# FlyControl.net
KiCad netlist of a schematic drawn in Altium Designer
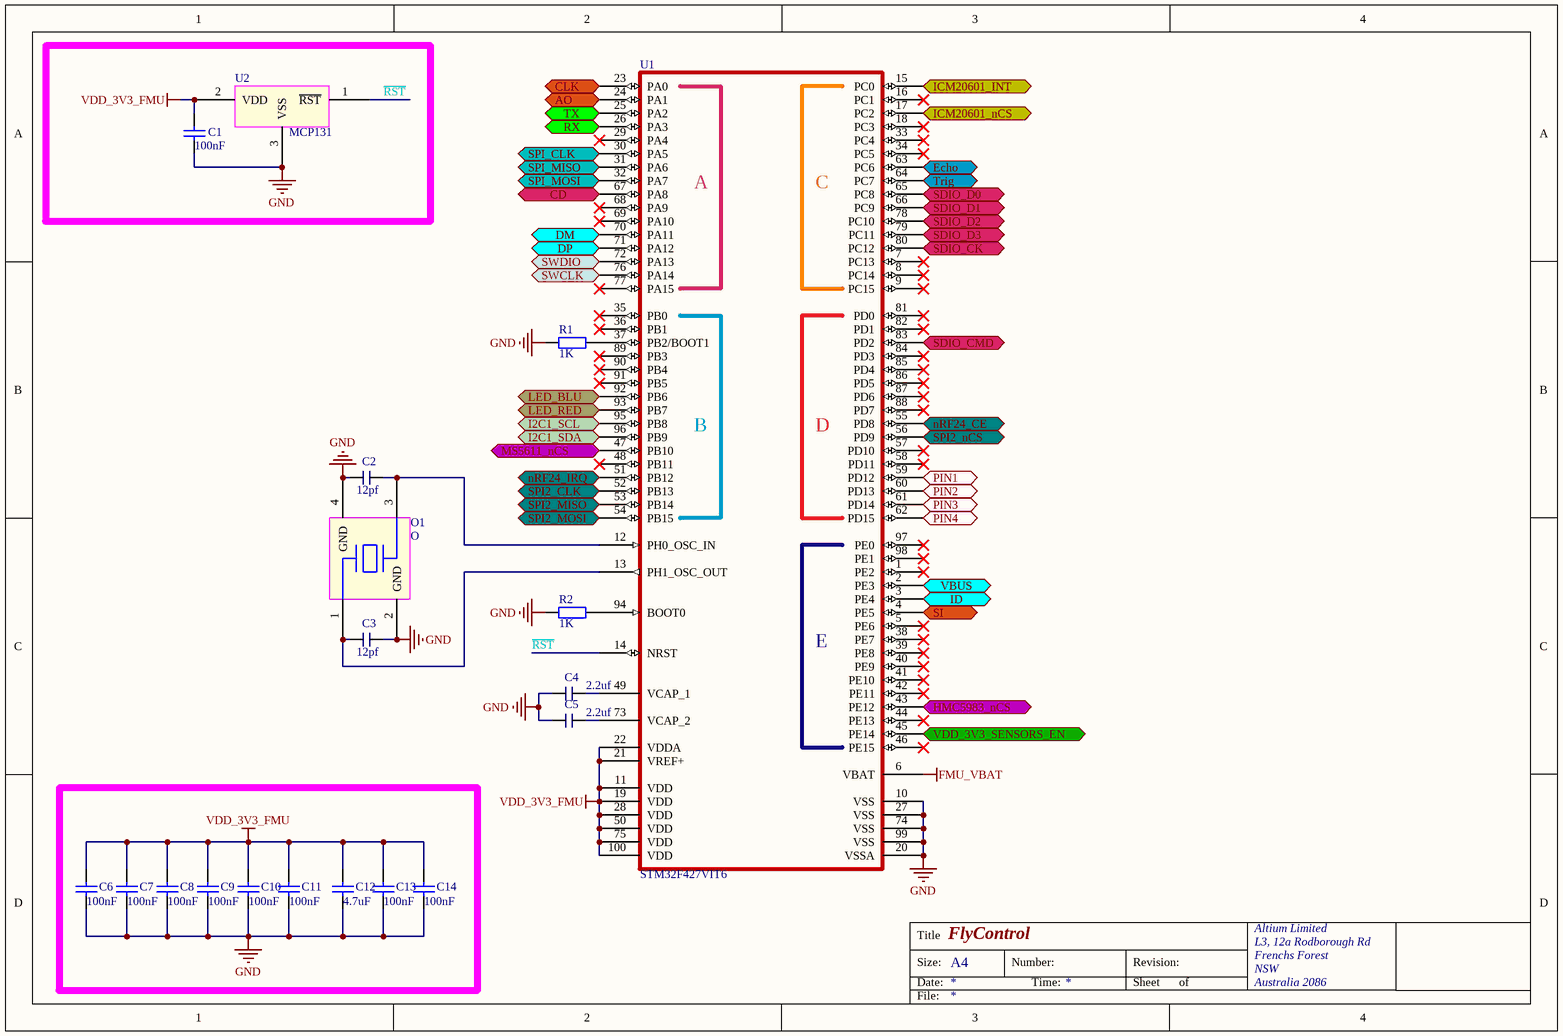
[diagram p0: FlyControl.SchDoc]

(export (version "E")
  (design (tool "Eeschema 10.0.6"))
  (components
    (comp (ref "C1")
      (value "100nF")
      (footprint "0603AC")
      (description "Capacitor")
      (fields (field (name "Comment") "Cap1") (field (name "PUBLISHER") "Altium Limited"))
      (libsource (lib "Component") (part "Cap1"))
    )
    (comp (ref "C2")
      (value "12pf")
      (footprint "0603AC")
      (fields (field (name "Comment") "Capacity"))
      (libsource (lib "Component") (part "Cap"))
    )
    (comp (ref "C3")
      (value "12pf")
      (footprint "0603AC")
      (fields (field (name "Comment") "Capacity"))
      (libsource (lib "Component") (part "Cap"))
    )
    (comp (ref "C4")
      (value "2.2uf")
      (footprint "0603AC")
      (fields (field (name "Comment") "Capacity"))
      (libsource (lib "Component") (part "Cap"))
    )
    (comp (ref "C5")
      (value "2.2uf")
      (footprint "0603AC")
      (fields (field (name "Comment") "Capacity"))
      (libsource (lib "Component") (part "Cap"))
    )
    (comp (ref "C6")
      (value "100nF")
      (footprint "0603AC")
      (description "Capacitor")
      (fields (field (name "Comment") "Cap1") (field (name "PUBLISHER") "Altium Limited"))
      (libsource (lib "Component") (part "Cap1"))
    )
    (comp (ref "C7")
      (value "100nF")
      (footprint "0603AC")
      (description "Capacitor")
      (fields (field (name "Comment") "Cap1") (field (name "PUBLISHER") "Altium Limited"))
      (libsource (lib "Component") (part "Cap1"))
    )
    (comp (ref "C8")
      (value "100nF")
      (footprint "0603AC")
      (description "Capacitor")
      (fields (field (name "Comment") "Cap1") (field (name "PUBLISHER") "Altium Limited"))
      (libsource (lib "Component") (part "Cap1"))
    )
    (comp (ref "C9")
      (value "100nF")
      (footprint "0603AC")
      (description "Capacitor")
      (fields (field (name "Comment") "Cap1") (field (name "PUBLISHER") "Altium Limited"))
      (libsource (lib "Component") (part "Cap1"))
    )
    (comp (ref "C10")
      (value "100nF")
      (footprint "0603AC")
      (description "Capacitor")
      (fields (field (name "Comment") "Cap1") (field (name "PUBLISHER") "Altium Limited"))
      (libsource (lib "Component") (part "Cap1"))
    )
    (comp (ref "C11")
      (value "100nF")
      (footprint "0603AC")
      (description "Capacitor")
      (fields (field (name "Comment") "Cap1") (field (name "PUBLISHER") "Altium Limited"))
      (libsource (lib "Component") (part "Cap1"))
    )
    (comp (ref "C12")
      (value "4.7uF")
      (footprint "0603AC")
      (description "Capacitor")
      (fields (field (name "Comment") "Cap1") (field (name "PUBLISHER") "Altium Limited"))
      (libsource (lib "Component") (part "Cap1"))
    )
    (comp (ref "C13")
      (value "100nF")
      (footprint "0603AC")
      (description "Capacitor")
      (fields (field (name "Comment") "Cap1") (field (name "PUBLISHER") "Altium Limited"))
      (libsource (lib "Component") (part "Cap1"))
    )
    (comp (ref "C14")
      (value "100nF")
      (footprint "0603AC")
      (description "Capacitor")
      (fields (field (name "Comment") "Cap1") (field (name "PUBLISHER") "Altium Limited"))
      (libsource (lib "Component") (part "Cap1"))
    )
    (comp (ref "O1") (value "O") (footprint "SMD_3225") (libsource (lib "Component") (part "OSC")))
    (comp (ref "R1")
      (value "1K")
      (footprint "0603AR")
      (fields (field (name "Comment") "Resist"))
      (libsource (lib "Component") (part "Res"))
    )
    (comp (ref "R2")
      (value "1K")
      (footprint "0603AR")
      (fields (field (name "Comment") "Resist"))
      (libsource (lib "Component") (part "Res"))
    )
    (comp (ref "U1")
      (value "STM32F427VIT6")
      (footprint "LQFP50P1600X1600X160-100N")
      (libsource (lib "Microprocessor") (part "STM32F427VIT6"))
    )
    (comp (ref "U2") (value "MCP131") (footprint "SOT23") (libsource (lib "Reset") (part "MCP131")))
  )
  (nets
    (net (code "1") (name "/AO") (class "Default")
      (node (ref "U1") (pin "24") (pinfunction "PA1_24") (pintype "bidirectional"))
    )
    (net (code "2") (name "/CD") (class "Default")
      (node (ref "U1") (pin "67") (pinfunction "PA8_67") (pintype "bidirectional"))
    )
    (net (code "3") (name "/CLK") (class "Default")
      (node (ref "U1") (pin "23") (pinfunction "PA0_23") (pintype "bidirectional"))
    )
    (net (code "4") (name "/DM") (class "Default")
      (node (ref "U1") (pin "70") (pinfunction "PA11_70") (pintype "bidirectional"))
    )
    (net (code "5") (name "/DP") (class "Default")
      (node (ref "U1") (pin "71") (pinfunction "PA12_71") (pintype "bidirectional"))
    )
    (net (code "6") (name "/Echo") (class "Default")
      (node (ref "U1") (pin "63") (pinfunction "PC6_63") (pintype "bidirectional"))
    )
    (net (code "7") (name "/HMC5983_nCS") (class "Default")
      (node (ref "U1") (pin "43") (pinfunction "PE12_43") (pintype "bidirectional"))
    )
    (net (code "8") (name "/I2C1_SCL") (class "Default")
      (node (ref "U1") (pin "95") (pinfunction "PB8_95") (pintype "bidirectional"))
    )
    (net (code "9") (name "/I2C1_SDA") (class "Default")
      (node (ref "U1") (pin "96") (pinfunction "PB9_96") (pintype "bidirectional"))
    )
    (net (code "10") (name "/ICM20601_INT") (class "Default")
      (node (ref "U1") (pin "15") (pinfunction "PC0_15") (pintype "bidirectional"))
    )
    (net (code "11") (name "/ICM20601_nCS") (class "Default")
      (node (ref "U1") (pin "17") (pinfunction "PC2_17") (pintype "bidirectional"))
    )
    (net (code "12") (name "/ID") (class "Default")
      (node (ref "U1") (pin "3") (pinfunction "PE4_3") (pintype "bidirectional"))
    )
    (net (code "13") (name "/LED_BLU") (class "Default")
      (node (ref "U1") (pin "92") (pinfunction "PB6_92") (pintype "bidirectional"))
    )
    (net (code "14") (name "/LED_RED") (class "Default")
      (node (ref "U1") (pin "93") (pinfunction "PB7_93") (pintype "bidirectional"))
    )
    (net (code "15") (name "/MS5611_nCS") (class "Default")
      (node (ref "U1") (pin "47") (pinfunction "PB10_47") (pintype "bidirectional"))
    )
    (net (code "16") (name "/PIN1") (class "Default")
      (node (ref "U1") (pin "59") (pinfunction "PD12_59") (pintype "bidirectional"))
    )
    (net (code "17") (name "/PIN2") (class "Default")
      (node (ref "U1") (pin "60") (pinfunction "PD13_60") (pintype "bidirectional"))
    )
    (net (code "18") (name "/PIN3") (class "Default")
      (node (ref "U1") (pin "61") (pinfunction "PD14_61") (pintype "bidirectional"))
    )
    (net (code "19") (name "/PIN4") (class "Default")
      (node (ref "U1") (pin "62") (pinfunction "PD15_62") (pintype "bidirectional"))
    )
    (net (code "20") (name "/RX") (class "Default")
      (node (ref "U1") (pin "26") (pinfunction "PA3_26") (pintype "bidirectional"))
    )
    (net (code "21") (name "/SDIO_CK") (class "Default")
      (node (ref "U1") (pin "80") (pinfunction "PC12_80") (pintype "bidirectional"))
    )
    (net (code "22") (name "/SDIO_CMD") (class "Default")
      (node (ref "U1") (pin "83") (pinfunction "PD2_83") (pintype "bidirectional"))
    )
    (net (code "23") (name "/SDIO_D0") (class "Default")
      (node (ref "U1") (pin "65") (pinfunction "PC8_65") (pintype "bidirectional"))
    )
    (net (code "24") (name "/SDIO_D1") (class "Default")
      (node (ref "U1") (pin "66") (pinfunction "PC9_66") (pintype "bidirectional"))
    )
    (net (code "25") (name "/SDIO_D2") (class "Default")
      (node (ref "U1") (pin "78") (pinfunction "PC10_78") (pintype "bidirectional"))
    )
    (net (code "26") (name "/SDIO_D3") (class "Default")
      (node (ref "U1") (pin "79") (pinfunction "PC11_79") (pintype "bidirectional"))
    )
    (net (code "27") (name "/SI") (class "Default")
      (node (ref "U1") (pin "4") (pinfunction "PE5_4") (pintype "bidirectional"))
    )
    (net (code "28") (name "/SPI2_CLK") (class "Default")
      (node (ref "U1") (pin "52") (pinfunction "PB13_52") (pintype "bidirectional"))
    )
    (net (code "29") (name "/SPI2_MISO") (class "Default")
      (node (ref "U1") (pin "53") (pinfunction "PB14_53") (pintype "bidirectional"))
    )
    (net (code "30") (name "/SPI2_MOSI") (class "Default")
      (node (ref "U1") (pin "54") (pinfunction "PB15_54") (pintype "bidirectional"))
    )
    (net (code "31") (name "/SPI2_nCS") (class "Default")
      (node (ref "U1") (pin "56") (pinfunction "PD9_56") (pintype "bidirectional"))
    )
    (net (code "32") (name "/SPI_CLK") (class "Default")
      (node (ref "U1") (pin "30") (pinfunction "PA5_30") (pintype "bidirectional"))
    )
    (net (code "33") (name "/SPI_MISO") (class "Default")
      (node (ref "U1") (pin "31") (pinfunction "PA6_31") (pintype "bidirectional"))
    )
    (net (code "34") (name "/SPI_MOSI") (class "Default")
      (node (ref "U1") (pin "32") (pinfunction "PA7_32") (pintype "bidirectional"))
    )
    (net (code "35") (name "/SWCLK") (class "Default")
      (node (ref "U1") (pin "76") (pinfunction "PA14_76") (pintype "bidirectional"))
    )
    (net (code "36") (name "/SWDIO") (class "Default")
      (node (ref "U1") (pin "72") (pinfunction "PA13_72") (pintype "bidirectional"))
    )
    (net (code "37") (name "/TX") (class "Default")
      (node (ref "U1") (pin "25") (pinfunction "PA2_25") (pintype "bidirectional"))
    )
    (net (code "38") (name "/Trig") (class "Default")
      (node (ref "U1") (pin "64") (pinfunction "PC7_64") (pintype "bidirectional"))
    )
    (net (code "39") (name "/VBUS") (class "Default")
      (node (ref "U1") (pin "2") (pinfunction "PE3_2") (pintype "bidirectional"))
    )
    (net (code "40") (name "/VDD_3V3_SENSORS_EN") (class "Default")
      (node (ref "U1") (pin "45") (pinfunction "PE14_45") (pintype "bidirectional"))
    )
    (net (code "41") (name "/nRF24_CE") (class "Default")
      (node (ref "U1") (pin "55") (pinfunction "PD8_55") (pintype "bidirectional"))
    )
    (net (code "42") (name "/nRF24_IRQ") (class "Default")
      (node (ref "U1") (pin "51") (pinfunction "PB12_51") (pintype "bidirectional"))
    )
    (net (code "43") (name "/~{RST}") (class "Default")
      (node (ref "U1") (pin "14") (pinfunction "NRST_14") (pintype "bidirectional"))
      (node (ref "U2") (pin "1") (pinfunction "~{RST}_1") (pintype "passive"))
    )
    (net (code "44") (name "FMU_VBAT") (class "Default")
      (node (ref "U1") (pin "6") (pinfunction "VBAT_6") (pintype "power_in"))
    )
    (net (code "45") (name "GND") (class "Default")
      (node (ref "C1") (pin "1") (pinfunction "1_1") (pintype "passive"))
      (node (ref "C10") (pin "1") (pinfunction "1_1") (pintype "passive"))
      (node (ref "C11") (pin "1") (pinfunction "1_1") (pintype "passive"))
      (node (ref "C12") (pin "1") (pinfunction "1_1") (pintype "passive"))
      (node (ref "C13") (pin "1") (pinfunction "1_1") (pintype "passive"))
      (node (ref "C14") (pin "1") (pinfunction "1_1") (pintype "passive"))
      (node (ref "C2") (pin "1") (pinfunction "1_1") (pintype "passive"))
      (node (ref "C3") (pin "2") (pinfunction "2_2") (pintype "passive"))
      (node (ref "C4") (pin "1") (pinfunction "1_1") (pintype "passive"))
      (node (ref "C5") (pin "1") (pinfunction "1_1") (pintype "passive"))
      (node (ref "C6") (pin "1") (pinfunction "1_1") (pintype "passive"))
      (node (ref "C7") (pin "1") (pinfunction "1_1") (pintype "passive"))
      (node (ref "C8") (pin "1") (pinfunction "1_1") (pintype "passive"))
      (node (ref "C9") (pin "1") (pinfunction "1_1") (pintype "passive"))
      (node (ref "O1") (pin "2") (pinfunction "GND_2") (pintype "passive"))
      (node (ref "O1") (pin "4") (pinfunction "GND_4") (pintype "passive"))
      (node (ref "R1") (pin "1") (pinfunction "1_1") (pintype "passive"))
      (node (ref "R2") (pin "1") (pinfunction "1_1") (pintype "passive"))
      (node (ref "U1") (pin "10") (pinfunction "VSS_10") (pintype "power_in"))
      (node (ref "U1") (pin "20") (pinfunction "VSSA_20") (pintype "power_in"))
      (node (ref "U1") (pin "27") (pinfunction "VSS_27") (pintype "power_in"))
      (node (ref "U1") (pin "74") (pinfunction "VSS_74") (pintype "power_in"))
      (node (ref "U1") (pin "99") (pinfunction "VSS_99") (pintype "power_in"))
      (node (ref "U2") (pin "3") (pinfunction "VSS_3") (pintype "passive"))
    )
    (net (code "46") (name "Net-(U1-BOOT0)") (class "Default")
      (node (ref "R2") (pin "2") (pinfunction "2_2") (pintype "passive"))
      (node (ref "U1") (pin "94") (pinfunction "BOOT0_94") (pintype "input"))
    )
    (net (code "47") (name "Net-(U1-PB2{slash}BOOT1)") (class "Default")
      (node (ref "R1") (pin "2") (pinfunction "2_2") (pintype "passive"))
      (node (ref "U1") (pin "37") (pinfunction "PB2/BOOT1_37") (pintype "bidirectional"))
    )
    (net (code "48") (name "Net-(U1-PH0_OSC_IN)") (class "Default")
      (node (ref "C2") (pin "2") (pinfunction "2_2") (pintype "passive"))
      (node (ref "O1") (pin "3") (pinfunction "OSC_3") (pintype "passive"))
      (node (ref "U1") (pin "12") (pinfunction "PH0_OSC_IN_12") (pintype "input"))
    )
    (net (code "49") (name "Net-(U1-PH1_OSC_OUT)") (class "Default")
      (node (ref "C3") (pin "1") (pinfunction "1_1") (pintype "passive"))
      (node (ref "O1") (pin "1") (pinfunction "OSC_1") (pintype "passive"))
      (node (ref "U1") (pin "13") (pinfunction "PH1_OSC_OUT_13") (pintype "output"))
    )
    (net (code "50") (name "Net-(U1-VCAP_1)") (class "Default")
      (node (ref "C4") (pin "2") (pinfunction "2_2") (pintype "passive"))
      (node (ref "U1") (pin "49") (pinfunction "VCAP_1_49") (pintype "passive"))
    )
    (net (code "51") (name "Net-(U1-VCAP_2)") (class "Default")
      (node (ref "C5") (pin "2") (pinfunction "2_2") (pintype "passive"))
      (node (ref "U1") (pin "73") (pinfunction "VCAP_2_73") (pintype "passive"))
    )
    (net (code "52") (name "VDD_3V3_FMU") (class "Default")
      (node (ref "C1") (pin "2") (pinfunction "2_2") (pintype "passive"))
      (node (ref "C10") (pin "2") (pinfunction "2_2") (pintype "passive"))
      (node (ref "C11") (pin "2") (pinfunction "2_2") (pintype "passive"))
      (node (ref "C12") (pin "2") (pinfunction "2_2") (pintype "passive"))
      (node (ref "C13") (pin "2") (pinfunction "2_2") (pintype "passive"))
      (node (ref "C14") (pin "2") (pinfunction "2_2") (pintype "passive"))
      (node (ref "C6") (pin "2") (pinfunction "2_2") (pintype "passive"))
      (node (ref "C7") (pin "2") (pinfunction "2_2") (pintype "passive"))
      (node (ref "C8") (pin "2") (pinfunction "2_2") (pintype "passive"))
      (node (ref "C9") (pin "2") (pinfunction "2_2") (pintype "passive"))
      (node (ref "U1") (pin "100") (pinfunction "VDD_100") (pintype "power_in"))
      (node (ref "U1") (pin "11") (pinfunction "VDD_11") (pintype "power_in"))
      (node (ref "U1") (pin "19") (pinfunction "VDD_19") (pintype "power_in"))
      (node (ref "U1") (pin "21") (pinfunction "VREF+_21") (pintype "power_in"))
      (node (ref "U1") (pin "22") (pinfunction "VDDA_22") (pintype "power_in"))
      (node (ref "U1") (pin "28") (pinfunction "VDD_28") (pintype "power_in"))
      (node (ref "U1") (pin "50") (pinfunction "VDD_50") (pintype "power_in"))
      (node (ref "U1") (pin "75") (pinfunction "VDD_75") (pintype "power_in"))
      (node (ref "U2") (pin "2") (pinfunction "VDD_2") (pintype "passive"))
    )
    (net (code "53") (name "unconnected-(U1-PA4-Pad29)") (class "Default")
      (node (ref "U1") (pin "29") (pinfunction "PA4_29") (pintype "bidirectional+no_connect"))
    )
    (net (code "54") (name "unconnected-(U1-PA9-Pad68)") (class "Default")
      (node (ref "U1") (pin "68") (pinfunction "PA9_68") (pintype "bidirectional+no_connect"))
    )
    (net (code "55") (name "unconnected-(U1-PA10-Pad69)") (class "Default")
      (node (ref "U1") (pin "69") (pinfunction "PA10_69") (pintype "bidirectional+no_connect"))
    )
    (net (code "56") (name "unconnected-(U1-PA15-Pad77)") (class "Default")
      (node (ref "U1") (pin "77") (pinfunction "PA15_77") (pintype "bidirectional+no_connect"))
    )
    (net (code "57") (name "unconnected-(U1-PB0-Pad35)") (class "Default")
      (node (ref "U1") (pin "35") (pinfunction "PB0_35") (pintype "bidirectional+no_connect"))
    )
    (net (code "58") (name "unconnected-(U1-PB1-Pad36)") (class "Default")
      (node (ref "U1") (pin "36") (pinfunction "PB1_36") (pintype "bidirectional+no_connect"))
    )
    (net (code "59") (name "unconnected-(U1-PB3-Pad89)") (class "Default")
      (node (ref "U1") (pin "89") (pinfunction "PB3_89") (pintype "bidirectional+no_connect"))
    )
    (net (code "60") (name "unconnected-(U1-PB4-Pad90)") (class "Default")
      (node (ref "U1") (pin "90") (pinfunction "PB4_90") (pintype "bidirectional+no_connect"))
    )
    (net (code "61") (name "unconnected-(U1-PB5-Pad91)") (class "Default")
      (node (ref "U1") (pin "91") (pinfunction "PB5_91") (pintype "bidirectional+no_connect"))
    )
    (net (code "62") (name "unconnected-(U1-PB11-Pad48)") (class "Default")
      (node (ref "U1") (pin "48") (pinfunction "PB11_48") (pintype "bidirectional+no_connect"))
    )
    (net (code "63") (name "unconnected-(U1-PC1-Pad16)") (class "Default")
      (node (ref "U1") (pin "16") (pinfunction "PC1_16") (pintype "bidirectional+no_connect"))
    )
    (net (code "64") (name "unconnected-(U1-PC3-Pad18)") (class "Default")
      (node (ref "U1") (pin "18") (pinfunction "PC3_18") (pintype "bidirectional+no_connect"))
    )
    (net (code "65") (name "unconnected-(U1-PC4-Pad33)") (class "Default")
      (node (ref "U1") (pin "33") (pinfunction "PC4_33") (pintype "bidirectional+no_connect"))
    )
    (net (code "66") (name "unconnected-(U1-PC5-Pad34)") (class "Default")
      (node (ref "U1") (pin "34") (pinfunction "PC5_34") (pintype "bidirectional+no_connect"))
    )
    (net (code "67") (name "unconnected-(U1-PC13-Pad7)") (class "Default")
      (node (ref "U1") (pin "7") (pinfunction "PC13_7") (pintype "bidirectional+no_connect"))
    )
    (net (code "68") (name "unconnected-(U1-PC14-Pad8)") (class "Default")
      (node (ref "U1") (pin "8") (pinfunction "PC14_8") (pintype "bidirectional+no_connect"))
    )
    (net (code "69") (name "unconnected-(U1-PC15-Pad9)") (class "Default")
      (node (ref "U1") (pin "9") (pinfunction "PC15_9") (pintype "bidirectional+no_connect"))
    )
    (net (code "70") (name "unconnected-(U1-PD0-Pad81)") (class "Default")
      (node (ref "U1") (pin "81") (pinfunction "PD0_81") (pintype "bidirectional+no_connect"))
    )
    (net (code "71") (name "unconnected-(U1-PD1-Pad82)") (class "Default")
      (node (ref "U1") (pin "82") (pinfunction "PD1_82") (pintype "bidirectional+no_connect"))
    )
    (net (code "72") (name "unconnected-(U1-PD3-Pad84)") (class "Default")
      (node (ref "U1") (pin "84") (pinfunction "PD3_84") (pintype "bidirectional+no_connect"))
    )
    (net (code "73") (name "unconnected-(U1-PD4-Pad85)") (class "Default")
      (node (ref "U1") (pin "85") (pinfunction "PD4_85") (pintype "bidirectional+no_connect"))
    )
    (net (code "74") (name "unconnected-(U1-PD5-Pad86)") (class "Default")
      (node (ref "U1") (pin "86") (pinfunction "PD5_86") (pintype "bidirectional+no_connect"))
    )
    (net (code "75") (name "unconnected-(U1-PD6-Pad87)") (class "Default")
      (node (ref "U1") (pin "87") (pinfunction "PD6_87") (pintype "bidirectional+no_connect"))
    )
    (net (code "76") (name "unconnected-(U1-PD7-Pad88)") (class "Default")
      (node (ref "U1") (pin "88") (pinfunction "PD7_88") (pintype "bidirectional+no_connect"))
    )
    (net (code "77") (name "unconnected-(U1-PD10-Pad57)") (class "Default")
      (node (ref "U1") (pin "57") (pinfunction "PD10_57") (pintype "bidirectional+no_connect"))
    )
    (net (code "78") (name "unconnected-(U1-PD11-Pad58)") (class "Default")
      (node (ref "U1") (pin "58") (pinfunction "PD11_58") (pintype "bidirectional+no_connect"))
    )
    (net (code "79") (name "unconnected-(U1-PE0-Pad97)") (class "Default")
      (node (ref "U1") (pin "97") (pinfunction "PE0_97") (pintype "bidirectional+no_connect"))
    )
    (net (code "80") (name "unconnected-(U1-PE1-Pad98)") (class "Default")
      (node (ref "U1") (pin "98") (pinfunction "PE1_98") (pintype "bidirectional+no_connect"))
    )
    (net (code "81") (name "unconnected-(U1-PE2-Pad1)") (class "Default")
      (node (ref "U1") (pin "1") (pinfunction "PE2_1") (pintype "bidirectional+no_connect"))
    )
    (net (code "82") (name "unconnected-(U1-PE6-Pad5)") (class "Default")
      (node (ref "U1") (pin "5") (pinfunction "PE6_5") (pintype "bidirectional+no_connect"))
    )
    (net (code "83") (name "unconnected-(U1-PE7-Pad38)") (class "Default")
      (node (ref "U1") (pin "38") (pinfunction "PE7_38") (pintype "bidirectional+no_connect"))
    )
    (net (code "84") (name "unconnected-(U1-PE8-Pad39)") (class "Default")
      (node (ref "U1") (pin "39") (pinfunction "PE8_39") (pintype "bidirectional+no_connect"))
    )
    (net (code "85") (name "unconnected-(U1-PE9-Pad40)") (class "Default")
      (node (ref "U1") (pin "40") (pinfunction "PE9_40") (pintype "bidirectional+no_connect"))
    )
    (net (code "86") (name "unconnected-(U1-PE10-Pad41)") (class "Default")
      (node (ref "U1") (pin "41") (pinfunction "PE10_41") (pintype "bidirectional+no_connect"))
    )
    (net (code "87") (name "unconnected-(U1-PE11-Pad42)") (class "Default")
      (node (ref "U1") (pin "42") (pinfunction "PE11_42") (pintype "bidirectional+no_connect"))
    )
    (net (code "88") (name "unconnected-(U1-PE13-Pad44)") (class "Default")
      (node (ref "U1") (pin "44") (pinfunction "PE13_44") (pintype "bidirectional+no_connect"))
    )
    (net (code "89") (name "unconnected-(U1-PE15-Pad46)") (class "Default")
      (node (ref "U1") (pin "46") (pinfunction "PE15_46") (pintype "bidirectional+no_connect"))
    )
  )
)
